# Models.net
KiCad netlist of a schematic drawn in Altium Designer
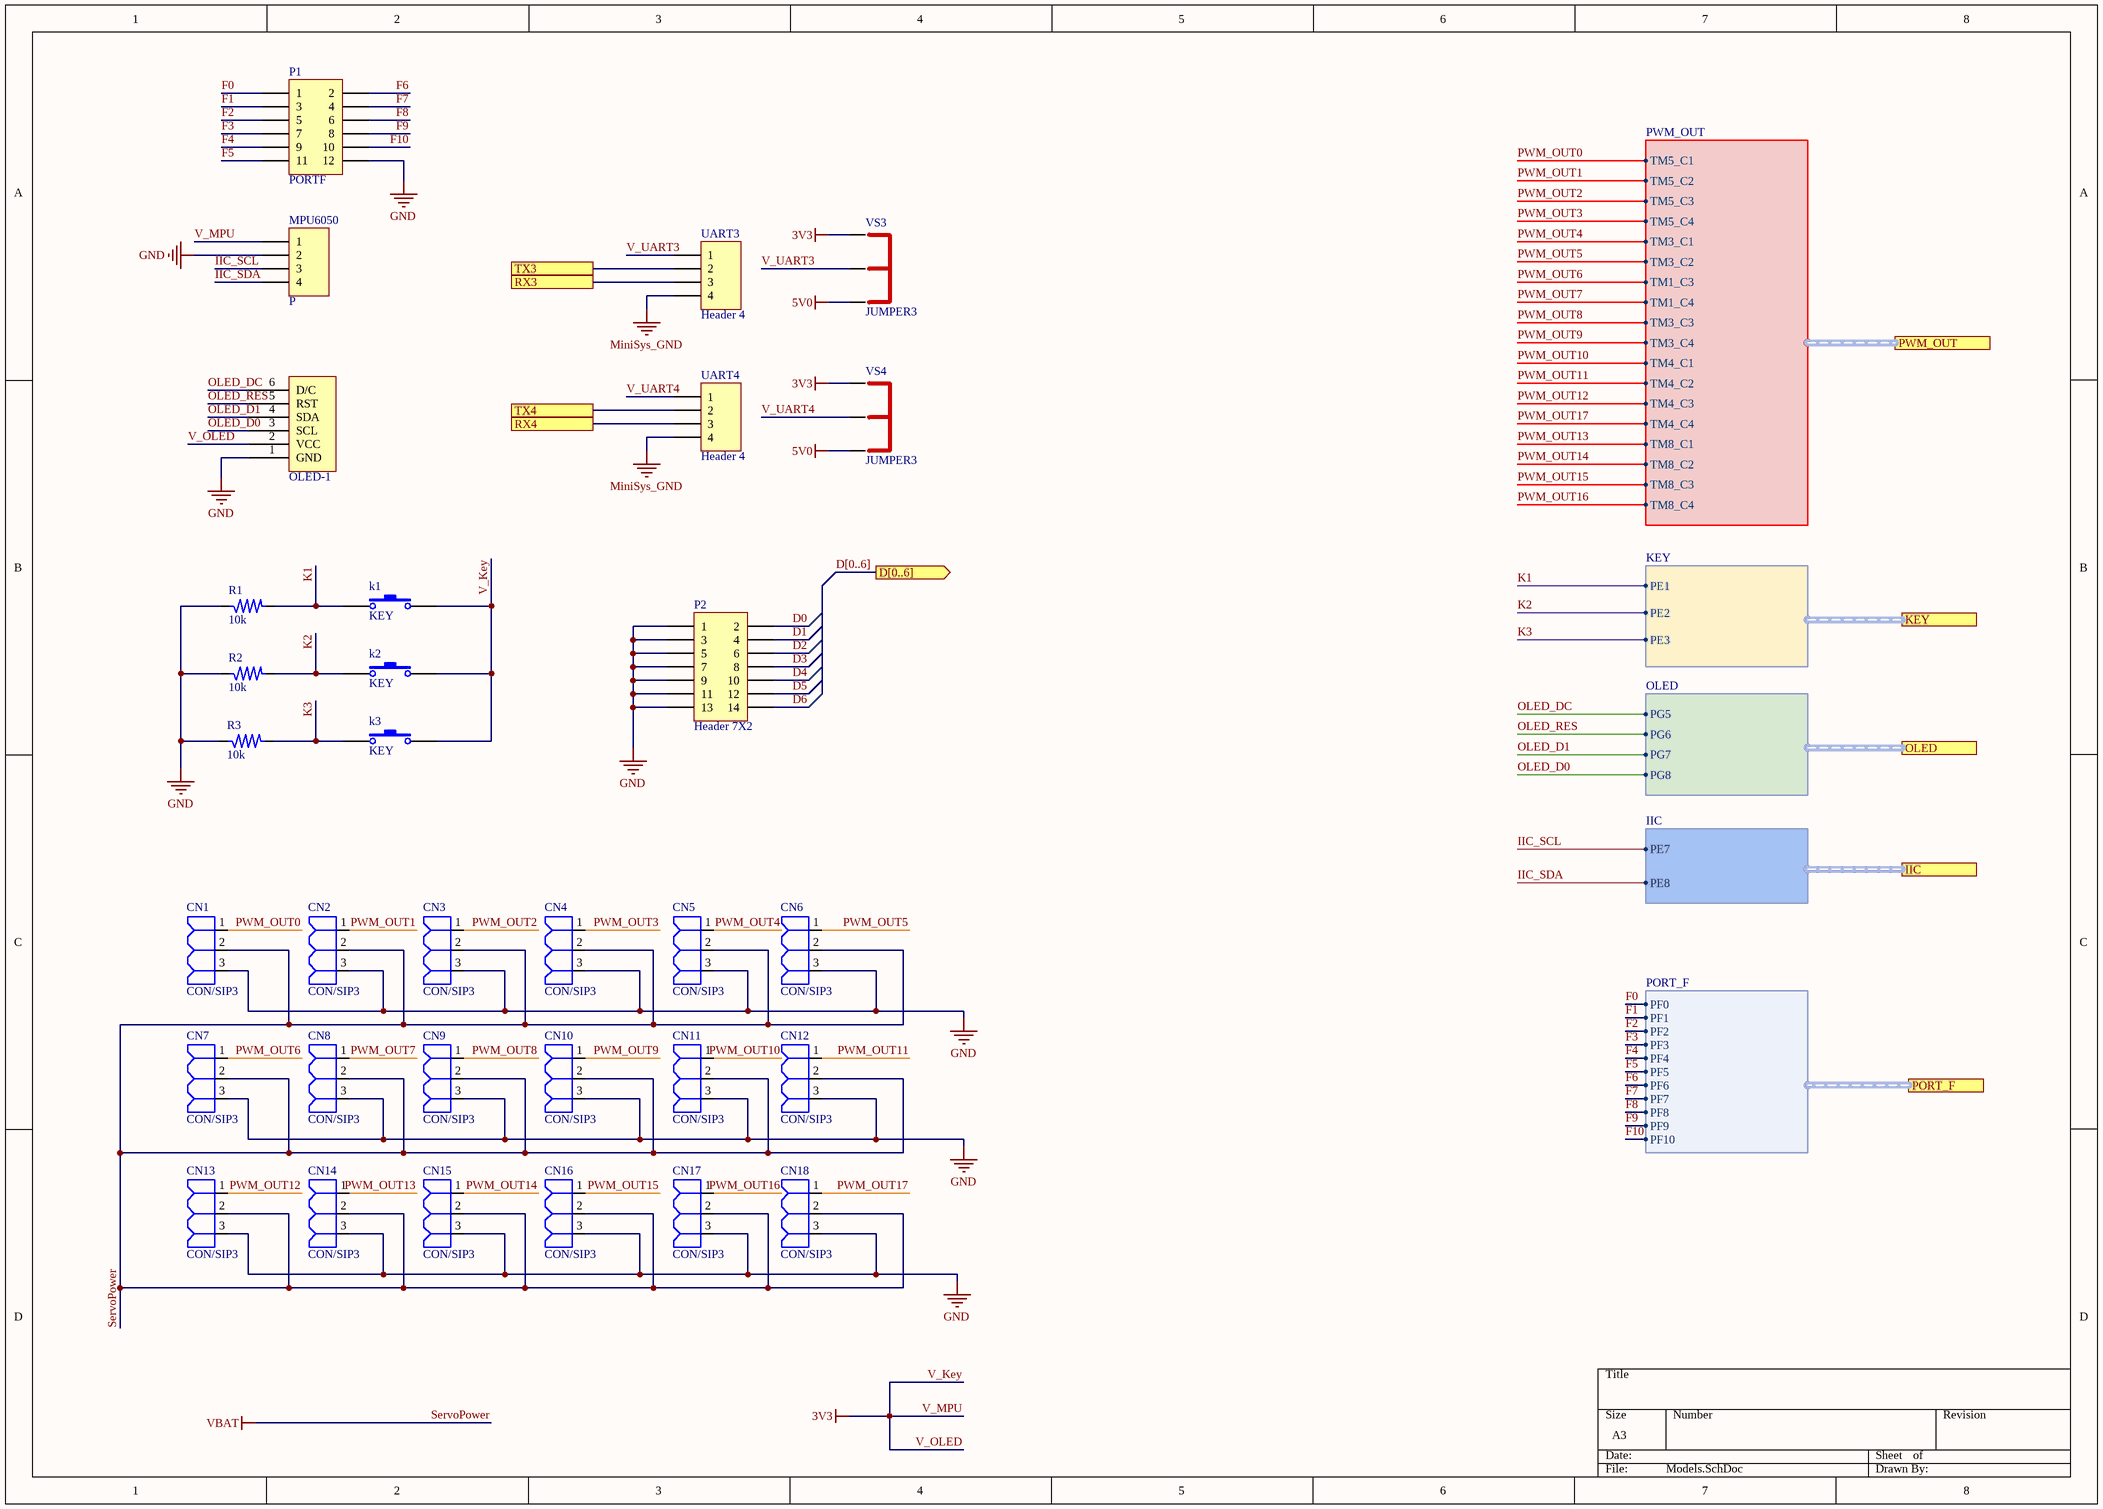
[diagram p0: Models.SchDoc]

(export (version "E")
  (design (tool "Eeschema 10.0.6"))
  (components
    (comp (ref "CN1")
      (value "CON/SIP3")
      (footprint "HDR1X3")
      (libsource (lib "LQ_Integrated_Library") (part "CON/SIP3"))
    )
    (comp (ref "CN2")
      (value "CON/SIP3")
      (footprint "HDR1X3")
      (libsource (lib "LQ_Integrated_Library") (part "CON/SIP3"))
    )
    (comp (ref "CN3")
      (value "CON/SIP3")
      (footprint "HDR1X3")
      (libsource (lib "LQ_Integrated_Library") (part "CON/SIP3"))
    )
    (comp (ref "CN4")
      (value "CON/SIP3")
      (footprint "HDR1X3")
      (libsource (lib "LQ_Integrated_Library") (part "CON/SIP3"))
    )
    (comp (ref "CN5")
      (value "CON/SIP3")
      (footprint "HDR1X3")
      (libsource (lib "LQ_Integrated_Library") (part "CON/SIP3"))
    )
    (comp (ref "CN6")
      (value "CON/SIP3")
      (footprint "HDR1X3")
      (libsource (lib "LQ_Integrated_Library") (part "CON/SIP3"))
    )
    (comp (ref "CN7")
      (value "CON/SIP3")
      (footprint "HDR1X3")
      (libsource (lib "LQ_Integrated_Library") (part "CON/SIP3"))
    )
    (comp (ref "CN8")
      (value "CON/SIP3")
      (footprint "HDR1X3")
      (libsource (lib "LQ_Integrated_Library") (part "CON/SIP3"))
    )
    (comp (ref "CN9")
      (value "CON/SIP3")
      (footprint "HDR1X3")
      (libsource (lib "LQ_Integrated_Library") (part "CON/SIP3"))
    )
    (comp (ref "CN10")
      (value "CON/SIP3")
      (footprint "HDR1X3")
      (libsource (lib "LQ_Integrated_Library") (part "CON/SIP3"))
    )
    (comp (ref "CN11")
      (value "CON/SIP3")
      (footprint "HDR1X3")
      (libsource (lib "LQ_Integrated_Library") (part "CON/SIP3"))
    )
    (comp (ref "CN12")
      (value "CON/SIP3")
      (footprint "HDR1X3")
      (libsource (lib "LQ_Integrated_Library") (part "CON/SIP3"))
    )
    (comp (ref "CN13")
      (value "CON/SIP3")
      (footprint "HDR1X3")
      (libsource (lib "LQ_Integrated_Library") (part "CON/SIP3"))
    )
    (comp (ref "CN14")
      (value "CON/SIP3")
      (footprint "HDR1X3")
      (libsource (lib "LQ_Integrated_Library") (part "CON/SIP3"))
    )
    (comp (ref "CN15")
      (value "CON/SIP3")
      (footprint "HDR1X3")
      (libsource (lib "LQ_Integrated_Library") (part "CON/SIP3"))
    )
    (comp (ref "CN16")
      (value "CON/SIP3")
      (footprint "HDR1X3")
      (libsource (lib "LQ_Integrated_Library") (part "CON/SIP3"))
    )
    (comp (ref "CN17")
      (value "CON/SIP3")
      (footprint "HDR1X3")
      (libsource (lib "LQ_Integrated_Library") (part "CON/SIP3"))
    )
    (comp (ref "CN18")
      (value "CON/SIP3")
      (footprint "HDR1X3")
      (libsource (lib "LQ_Integrated_Library") (part "CON/SIP3"))
    )
    (comp (ref "k1") (value "KEY") (footprint "按键-贴片-1") (libsource (lib "APPPCB") (part "按键")))
    (comp (ref "k2") (value "KEY") (footprint "按键-贴片-1") (libsource (lib "APPPCB") (part "按键")))
    (comp (ref "k3") (value "KEY") (footprint "按键-贴片-1") (libsource (lib "APPPCB") (part "按键")))
    (comp (ref "MPU6050")
      (value "P")
      (footprint "HDR1X4")
      (description "Header, 4-Pin")
      (fields (field (name "PUBLISHER") "Altium Limited"))
      (libsource (lib "Miscellaneous Connectors") (part "Header 4"))
    )
    (comp (ref "OLED-1") (value "OLED直插") (footprint "OLED直插") (libsource (lib "APPPCB") (part "OLED直插")))
    (comp (ref "P1")
      (value "PORTF")
      (footprint "HDR2X6")
      (description "Header, 6-Pin, Dual row")
      (fields (field (name "PUBLISHER") "Altium Limited"))
      (libsource (lib "Miscellaneous Connectors") (part "Header 6X2"))
    )
    (comp (ref "P2")
      (value "Header 7X2")
      (footprint "HDR2X7")
      (description "Header, 7-Pin, Dual row")
      (fields (field (name "PUBLISHER") "Altium Limited"))
      (libsource (lib "Miscellaneous Connectors") (part "Header 7X2"))
    )
    (comp (ref "R1")
      (value "10k")
      (footprint "R0805")
      (description "电阻")
      (libsource (lib "LQ_Integrated_Library") (part "Resistor"))
    )
    (comp (ref "R2")
      (value "10k")
      (footprint "R0805")
      (description "电阻")
      (libsource (lib "LQ_Integrated_Library") (part "Resistor"))
    )
    (comp (ref "R3")
      (value "10k")
      (footprint "R0805")
      (description "电阻")
      (libsource (lib "LQ_Integrated_Library") (part "Resistor"))
    )
    (comp (ref "UART3")
      (value "Header 4")
      (footprint "HDR1X4")
      (description "Header, 4-Pin")
      (fields (field (name "PUBLISHER") "Altium Limited"))
      (libsource (lib "Miscellaneous Connectors") (part "Header 4"))
    )
    (comp (ref "UART4")
      (value "Header 4")
      (footprint "HDR1X4")
      (description "Header, 4-Pin")
      (fields (field (name "PUBLISHER") "Altium Limited"))
      (libsource (lib "Miscellaneous Connectors") (part "Header 4"))
    )
    (comp (ref "VS3")
      (value "JUMPER3")
      (footprint "Jumper3")
      (description "Jumper")
      (libsource (lib "LQ_Integrated_Library") (part "JUMPER3"))
    )
    (comp (ref "VS4")
      (value "JUMPER3")
      (footprint "Jumper3")
      (description "Jumper")
      (libsource (lib "LQ_Integrated_Library") (part "JUMPER3"))
    )
  )
  (nets
    (net (code "6") (name "/D0") (class "Default")
      (node (ref "P2") (pin "2") (pinfunction "2_2") (pintype "passive"))
    )
    (net (code "7") (name "/D1") (class "Default")
      (node (ref "P2") (pin "4") (pinfunction "4_4") (pintype "passive"))
    )
    (net (code "8") (name "/D2") (class "Default")
      (node (ref "P2") (pin "6") (pinfunction "6_6") (pintype "passive"))
    )
    (net (code "9") (name "/D3") (class "Default")
      (node (ref "P2") (pin "8") (pinfunction "8_8") (pintype "passive"))
    )
    (net (code "10") (name "/D4") (class "Default")
      (node (ref "P2") (pin "10") (pinfunction "10_10") (pintype "passive"))
    )
    (net (code "11") (name "/D5") (class "Default")
      (node (ref "P2") (pin "12") (pinfunction "12_12") (pintype "passive"))
    )
    (net (code "12") (name "/D6") (class "Default")
      (node (ref "P2") (pin "14") (pinfunction "14_14") (pintype "passive"))
    )
    (net (code "14") (name "/F0") (class "Default")
      (node (ref "P1") (pin "1") (pinfunction "1_1") (pintype "passive"))
    )
    (net (code "15") (name "/F1") (class "Default")
      (node (ref "P1") (pin "3") (pinfunction "3_3") (pintype "passive"))
    )
    (net (code "16") (name "/F2") (class "Default")
      (node (ref "P1") (pin "5") (pinfunction "5_5") (pintype "passive"))
    )
    (net (code "17") (name "/F3") (class "Default")
      (node (ref "P1") (pin "7") (pinfunction "7_7") (pintype "passive"))
    )
    (net (code "18") (name "/F4") (class "Default")
      (node (ref "P1") (pin "9") (pinfunction "9_9") (pintype "passive"))
    )
    (net (code "19") (name "/F5") (class "Default")
      (node (ref "P1") (pin "11") (pinfunction "11_11") (pintype "passive"))
    )
    (net (code "20") (name "/F6") (class "Default")
      (node (ref "P1") (pin "2") (pinfunction "2_2") (pintype "passive"))
    )
    (net (code "21") (name "/F7") (class "Default")
      (node (ref "P1") (pin "4") (pinfunction "4_4") (pintype "passive"))
    )
    (net (code "22") (name "/F8") (class "Default")
      (node (ref "P1") (pin "6") (pinfunction "6_6") (pintype "passive"))
    )
    (net (code "23") (name "/F9") (class "Default")
      (node (ref "P1") (pin "8") (pinfunction "8_8") (pintype "passive"))
    )
    (net (code "24") (name "/F10") (class "Default")
      (node (ref "P1") (pin "10") (pinfunction "10_10") (pintype "passive"))
    )
    (net (code "25") (name "/IIC_SCL") (class "Default")
      (node (ref "MPU6050") (pin "3") (pinfunction "3_3") (pintype "passive"))
    )
    (net (code "26") (name "/IIC_SDA") (class "Default")
      (node (ref "MPU6050") (pin "4") (pinfunction "4_4") (pintype "passive"))
    )
    (net (code "27") (name "/K1") (class "Default")
      (node (ref "R1") (pin "1") (pinfunction "1_1") (pintype "passive"))
      (node (ref "k1") (pin "1") (pinfunction "1_1") (pintype "passive"))
    )
    (net (code "28") (name "/K2") (class "Default")
      (node (ref "R2") (pin "1") (pinfunction "1_1") (pintype "passive"))
      (node (ref "k2") (pin "1") (pinfunction "1_1") (pintype "passive"))
    )
    (net (code "29") (name "/K3") (class "Default")
      (node (ref "R3") (pin "1") (pinfunction "1_1") (pintype "passive"))
      (node (ref "k3") (pin "1") (pinfunction "1_1") (pintype "passive"))
    )
    (net (code "30") (name "/OLED_D0") (class "Default")
      (node (ref "OLED-1") (pin "3") (pinfunction "SCL_3") (pintype "passive"))
    )
    (net (code "31") (name "/OLED_D1") (class "Default")
      (node (ref "OLED-1") (pin "4") (pinfunction "SDA_4") (pintype "passive"))
    )
    (net (code "32") (name "/OLED_DC") (class "Default")
      (node (ref "OLED-1") (pin "6") (pinfunction "D/C_6") (pintype "passive"))
    )
    (net (code "33") (name "/OLED_RES") (class "Default")
      (node (ref "OLED-1") (pin "5") (pinfunction "RST_5") (pintype "passive"))
    )
    (net (code "34") (name "/PWM_OUT0") (class "Default") (node (ref "CN1") (pin "1") (pintype "passive")))
    (net (code "35") (name "/PWM_OUT1") (class "Default") (node (ref "CN2") (pin "1") (pintype "passive")))
    (net (code "36") (name "/PWM_OUT2") (class "Default") (node (ref "CN3") (pin "1") (pintype "passive")))
    (net (code "37") (name "/PWM_OUT3") (class "Default") (node (ref "CN4") (pin "1") (pintype "passive")))
    (net (code "38") (name "/PWM_OUT4") (class "Default") (node (ref "CN5") (pin "1") (pintype "passive")))
    (net (code "39") (name "/PWM_OUT5") (class "Default") (node (ref "CN6") (pin "1") (pintype "passive")))
    (net (code "40") (name "/PWM_OUT6") (class "Default") (node (ref "CN7") (pin "1") (pintype "passive")))
    (net (code "41") (name "/PWM_OUT7") (class "Default") (node (ref "CN8") (pin "1") (pintype "passive")))
    (net (code "42") (name "/PWM_OUT8") (class "Default") (node (ref "CN9") (pin "1") (pintype "passive")))
    (net (code "43") (name "/PWM_OUT9") (class "Default") (node (ref "CN10") (pin "1") (pintype "passive")))
    (net (code "44") (name "/PWM_OUT10") (class "Default") (node (ref "CN11") (pin "1") (pintype "passive")))
    (net (code "45") (name "/PWM_OUT11") (class "Default") (node (ref "CN12") (pin "1") (pintype "passive")))
    (net (code "46") (name "/PWM_OUT12") (class "Default") (node (ref "CN13") (pin "1") (pintype "passive")))
    (net (code "47") (name "/PWM_OUT13") (class "Default") (node (ref "CN14") (pin "1") (pintype "passive")))
    (net (code "48") (name "/PWM_OUT14") (class "Default") (node (ref "CN15") (pin "1") (pintype "passive")))
    (net (code "49") (name "/PWM_OUT15") (class "Default") (node (ref "CN16") (pin "1") (pintype "passive")))
    (net (code "50") (name "/PWM_OUT16") (class "Default") (node (ref "CN17") (pin "1") (pintype "passive")))
    (net (code "51") (name "/PWM_OUT17") (class "Default") (node (ref "CN18") (pin "1") (pintype "passive")))
    (net (code "52") (name "/RX3") (class "Default")
      (node (ref "UART3") (pin "3") (pinfunction "3_3") (pintype "passive"))
    )
    (net (code "53") (name "/RX4") (class "Default")
      (node (ref "UART4") (pin "3") (pinfunction "3_3") (pintype "passive"))
    )
    (net (code "54") (name "/TX3") (class "Default")
      (node (ref "UART3") (pin "2") (pinfunction "2_2") (pintype "passive"))
    )
    (net (code "55") (name "/TX4") (class "Default")
      (node (ref "UART4") (pin "2") (pinfunction "2_2") (pintype "passive"))
    )
    (net (code "56") (name "/V_UART3") (class "Default")
      (node (ref "UART3") (pin "1") (pinfunction "1_1") (pintype "passive"))
      (node (ref "VS3") (pin "2") (pinfunction "2_2") (pintype "passive"))
    )
    (net (code "57") (name "/V_UART4") (class "Default")
      (node (ref "UART4") (pin "1") (pinfunction "1_1") (pintype "passive"))
      (node (ref "VS4") (pin "2") (pinfunction "2_2") (pintype "passive"))
    )
    (net (code "63") (name "3V3") (class "Default")
      (node (ref "MPU6050") (pin "1") (pinfunction "1_1") (pintype "passive"))
      (node (ref "OLED-1") (pin "2") (pinfunction "VCC_2") (pintype "passive"))
      (node (ref "VS3") (pin "1") (pinfunction "1_1") (pintype "passive"))
      (node (ref "VS4") (pin "1") (pinfunction "1_1") (pintype "passive"))
      (node (ref "k1") (pin "2") (pinfunction "2_2") (pintype "passive"))
      (node (ref "k2") (pin "2") (pinfunction "2_2") (pintype "passive"))
      (node (ref "k3") (pin "2") (pinfunction "2_2") (pintype "passive"))
    )
    (net (code "64") (name "5V0") (class "Default")
      (node (ref "VS3") (pin "3") (pinfunction "3_3") (pintype "passive"))
      (node (ref "VS4") (pin "3") (pinfunction "3_3") (pintype "passive"))
    )
    (net (code "65") (name "GND") (class "Default")
      (node (ref "CN1") (pin "3") (pintype "passive"))
      (node (ref "CN10") (pin "3") (pintype "passive"))
      (node (ref "CN11") (pin "3") (pintype "passive"))
      (node (ref "CN12") (pin "3") (pintype "passive"))
      (node (ref "CN13") (pin "3") (pintype "passive"))
      (node (ref "CN14") (pin "3") (pintype "passive"))
      (node (ref "CN15") (pin "3") (pintype "passive"))
      (node (ref "CN16") (pin "3") (pintype "passive"))
      (node (ref "CN17") (pin "3") (pintype "passive"))
      (node (ref "CN18") (pin "3") (pintype "passive"))
      (node (ref "CN2") (pin "3") (pintype "passive"))
      (node (ref "CN3") (pin "3") (pintype "passive"))
      (node (ref "CN4") (pin "3") (pintype "passive"))
      (node (ref "CN5") (pin "3") (pintype "passive"))
      (node (ref "CN6") (pin "3") (pintype "passive"))
      (node (ref "CN7") (pin "3") (pintype "passive"))
      (node (ref "CN8") (pin "3") (pintype "passive"))
      (node (ref "CN9") (pin "3") (pintype "passive"))
      (node (ref "MPU6050") (pin "2") (pinfunction "2_2") (pintype "passive"))
      (node (ref "OLED-1") (pin "1") (pinfunction "GND_1") (pintype "passive"))
      (node (ref "P1") (pin "12") (pinfunction "12_12") (pintype "passive"))
      (node (ref "P2") (pin "1") (pinfunction "1_1") (pintype "passive"))
      (node (ref "P2") (pin "11") (pinfunction "11_11") (pintype "passive"))
      (node (ref "P2") (pin "13") (pinfunction "13_13") (pintype "passive"))
      (node (ref "P2") (pin "3") (pinfunction "3_3") (pintype "passive"))
      (node (ref "P2") (pin "5") (pinfunction "5_5") (pintype "passive"))
      (node (ref "P2") (pin "7") (pinfunction "7_7") (pintype "passive"))
      (node (ref "P2") (pin "9") (pinfunction "9_9") (pintype "passive"))
      (node (ref "R1") (pin "2") (pinfunction "2_2") (pintype "passive"))
      (node (ref "R2") (pin "2") (pinfunction "2_2") (pintype "passive"))
      (node (ref "R3") (pin "2") (pinfunction "2_2") (pintype "passive"))
    )
    (net (code "66") (name "MiniSys_GND") (class "Default")
      (node (ref "UART3") (pin "4") (pinfunction "4_4") (pintype "passive"))
      (node (ref "UART4") (pin "4") (pinfunction "4_4") (pintype "passive"))
    )
    (net (code "67") (name "VBAT") (class "Default")
      (node (ref "CN1") (pin "2") (pintype "passive"))
      (node (ref "CN10") (pin "2") (pintype "passive"))
      (node (ref "CN11") (pin "2") (pintype "passive"))
      (node (ref "CN12") (pin "2") (pintype "passive"))
      (node (ref "CN13") (pin "2") (pintype "passive"))
      (node (ref "CN14") (pin "2") (pintype "passive"))
      (node (ref "CN15") (pin "2") (pintype "passive"))
      (node (ref "CN16") (pin "2") (pintype "passive"))
      (node (ref "CN17") (pin "2") (pintype "passive"))
      (node (ref "CN18") (pin "2") (pintype "passive"))
      (node (ref "CN2") (pin "2") (pintype "passive"))
      (node (ref "CN3") (pin "2") (pintype "passive"))
      (node (ref "CN4") (pin "2") (pintype "passive"))
      (node (ref "CN5") (pin "2") (pintype "passive"))
      (node (ref "CN6") (pin "2") (pintype "passive"))
      (node (ref "CN7") (pin "2") (pintype "passive"))
      (node (ref "CN8") (pin "2") (pintype "passive"))
      (node (ref "CN9") (pin "2") (pintype "passive"))
    )
  )
)
